# custom_line_V1_mux5.net
KiCad netlist of a schematic drawn in Altium Designer
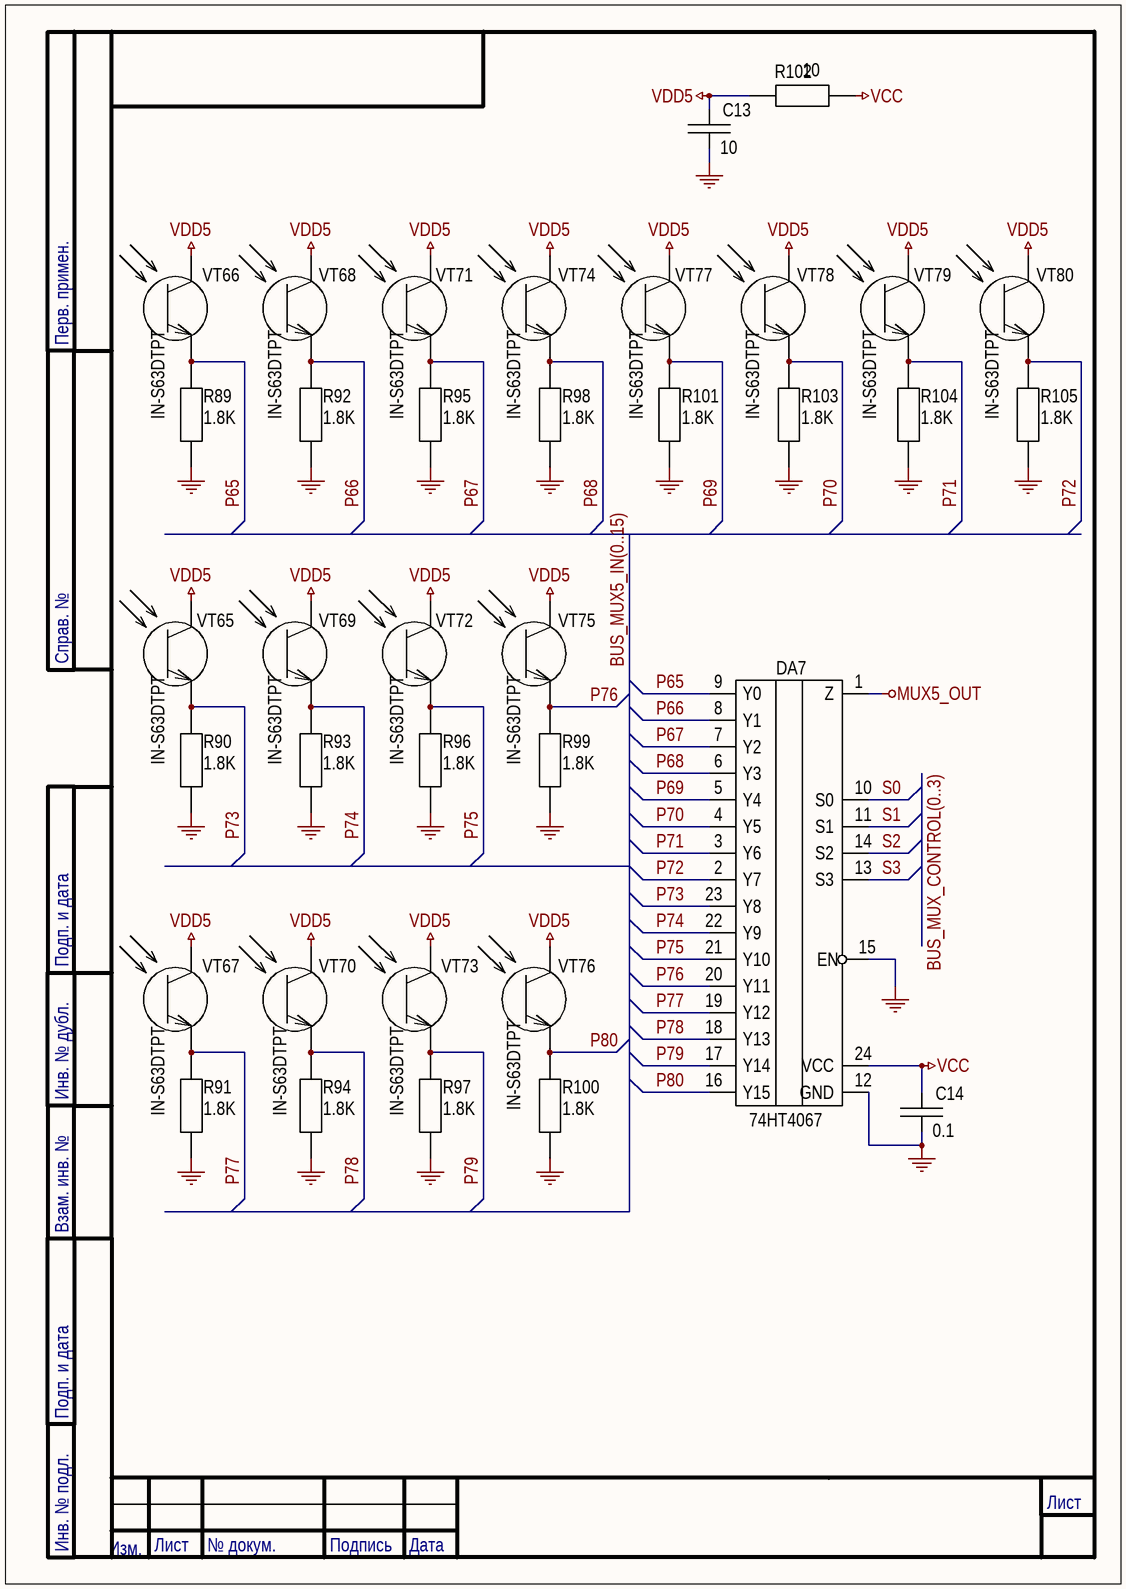
[diagram p0: custom_line_V1_mux5.SchDoc]

(export (version "E")
  (design (tool "Eeschema 10.0.6"))
  (components
    (comp (ref "C13") (value "10") (footprint "CC_0805") (libsource (lib "my_discrete_new") (part "C")))
    (comp (ref "C14") (value "0.1") (footprint "CC_0603") (libsource (lib "my_discrete_new") (part "C")))
    (comp (ref "DA7")
      (value "74HC4067")
      (footprint "TSSOP-24")
      (description "74HC4067PW")
      (fields (field (name "TYPE") "74HT4067"))
      (libsource (lib "my_microschems_new") (part "74HCT4067"))
    )
    (comp (ref "R89")
      (value "1.8K")
      (footprint "RC_0603_SMALL")
      (fields (field (name "POWER") "0.125W"))
      (libsource (lib "my_discrete_new") (part "R"))
    )
    (comp (ref "R90")
      (value "1.8K")
      (footprint "RC_0603_SMALL")
      (fields (field (name "POWER") "0.125W"))
      (libsource (lib "my_discrete_new") (part "R"))
    )
    (comp (ref "R91")
      (value "1.8K")
      (footprint "RC_0603_SMALL")
      (fields (field (name "POWER") "0.125W"))
      (libsource (lib "my_discrete_new") (part "R"))
    )
    (comp (ref "R92")
      (value "1.8K")
      (footprint "RC_0603_SMALL")
      (fields (field (name "POWER") "0.125W"))
      (libsource (lib "my_discrete_new") (part "R"))
    )
    (comp (ref "R93")
      (value "1.8K")
      (footprint "RC_0603_SMALL")
      (fields (field (name "POWER") "0.125W"))
      (libsource (lib "my_discrete_new") (part "R"))
    )
    (comp (ref "R94")
      (value "1.8K")
      (footprint "RC_0603_SMALL")
      (fields (field (name "POWER") "0.125W"))
      (libsource (lib "my_discrete_new") (part "R"))
    )
    (comp (ref "R95")
      (value "1.8K")
      (footprint "RC_0603_SMALL")
      (fields (field (name "POWER") "0.125W"))
      (libsource (lib "my_discrete_new") (part "R"))
    )
    (comp (ref "R96")
      (value "1.8K")
      (footprint "RC_0603_SMALL")
      (fields (field (name "POWER") "0.125W"))
      (libsource (lib "my_discrete_new") (part "R"))
    )
    (comp (ref "R97")
      (value "1.8K")
      (footprint "RC_0603_SMALL")
      (fields (field (name "POWER") "0.125W"))
      (libsource (lib "my_discrete_new") (part "R"))
    )
    (comp (ref "R98")
      (value "1.8K")
      (footprint "RC_0603_SMALL")
      (fields (field (name "POWER") "0.125W"))
      (libsource (lib "my_discrete_new") (part "R"))
    )
    (comp (ref "R99")
      (value "1.8K")
      (footprint "RC_0603_SMALL")
      (fields (field (name "POWER") "0.125W"))
      (libsource (lib "my_discrete_new") (part "R"))
    )
    (comp (ref "R100")
      (value "1.8K")
      (footprint "RC_0603_SMALL")
      (fields (field (name "POWER") "0.125W"))
      (libsource (lib "my_discrete_new") (part "R"))
    )
    (comp (ref "R101")
      (value "1.8K")
      (footprint "RC_0603_SMALL")
      (fields (field (name "POWER") "0.125W"))
      (libsource (lib "my_discrete_new") (part "R"))
    )
    (comp (ref "R102")
      (value "10")
      (footprint "RC_0603_SMALL")
      (fields (field (name "POWER") "0.125W"))
      (libsource (lib "my_discrete_new") (part "R"))
    )
    (comp (ref "R103")
      (value "1.8K")
      (footprint "RC_0603_SMALL")
      (fields (field (name "POWER") "0.125W"))
      (libsource (lib "my_discrete_new") (part "R"))
    )
    (comp (ref "R104")
      (value "1.8K")
      (footprint "RC_0603_SMALL")
      (fields (field (name "POWER") "0.125W"))
      (libsource (lib "my_discrete_new") (part "R"))
    )
    (comp (ref "R105")
      (value "1.8K")
      (footprint "RC_0603_SMALL")
      (fields (field (name "POWER") "0.125W"))
      (libsource (lib "my_discrete_new") (part "R"))
    )
    (comp (ref "VT65")
      (value "IN-S63DTPT")
      (footprint "LED_0603")
      (description "Phototransistor (Inolux)")
      (libsource (lib "my_discrete_new") (part "phototransistor"))
    )
    (comp (ref "VT66")
      (value "IN-S63DTPT")
      (footprint "LED_0603")
      (description "Phototransistor (Inolux)")
      (libsource (lib "my_discrete_new") (part "phototransistor"))
    )
    (comp (ref "VT67")
      (value "IN-S63DTPT")
      (footprint "LED_0603")
      (description "Phototransistor (Inolux)")
      (libsource (lib "my_discrete_new") (part "phototransistor"))
    )
    (comp (ref "VT68")
      (value "IN-S63DTPT")
      (footprint "LED_0603")
      (description "Phototransistor (Inolux)")
      (libsource (lib "my_discrete_new") (part "phototransistor"))
    )
    (comp (ref "VT69")
      (value "IN-S63DTPT")
      (footprint "LED_0603")
      (description "Phototransistor (Inolux)")
      (libsource (lib "my_discrete_new") (part "phototransistor"))
    )
    (comp (ref "VT70")
      (value "IN-S63DTPT")
      (footprint "LED_0603")
      (description "Phototransistor (Inolux)")
      (libsource (lib "my_discrete_new") (part "phototransistor"))
    )
    (comp (ref "VT71")
      (value "IN-S63DTPT")
      (footprint "LED_0603")
      (description "Phototransistor (Inolux)")
      (libsource (lib "my_discrete_new") (part "phototransistor"))
    )
    (comp (ref "VT72")
      (value "IN-S63DTPT")
      (footprint "LED_0603")
      (description "Phototransistor (Inolux)")
      (libsource (lib "my_discrete_new") (part "phototransistor"))
    )
    (comp (ref "VT73")
      (value "IN-S63DTPT")
      (footprint "LED_0603")
      (description "Phototransistor (Inolux)")
      (libsource (lib "my_discrete_new") (part "phototransistor"))
    )
    (comp (ref "VT74")
      (value "IN-S63DTPT")
      (footprint "LED_0603")
      (description "Phototransistor (Inolux)")
      (libsource (lib "my_discrete_new") (part "phototransistor"))
    )
    (comp (ref "VT75")
      (value "IN-S63DTPT")
      (footprint "LED_0603")
      (description "Phototransistor (Inolux)")
      (libsource (lib "my_discrete_new") (part "phototransistor"))
    )
    (comp (ref "VT76")
      (value "IN-S63DTPT")
      (footprint "LED_0603")
      (description "Phototransistor (Inolux)")
      (libsource (lib "my_discrete_new") (part "phototransistor"))
    )
    (comp (ref "VT77")
      (value "IN-S63DTPT")
      (footprint "LED_0603")
      (description "Phototransistor (Inolux)")
      (libsource (lib "my_discrete_new") (part "phototransistor"))
    )
    (comp (ref "VT78")
      (value "IN-S63DTPT")
      (footprint "LED_0603")
      (description "Phototransistor (Inolux)")
      (libsource (lib "my_discrete_new") (part "phototransistor"))
    )
    (comp (ref "VT79")
      (value "IN-S63DTPT")
      (footprint "LED_0603")
      (description "Phototransistor (Inolux)")
      (libsource (lib "my_discrete_new") (part "phototransistor"))
    )
    (comp (ref "VT80")
      (value "IN-S63DTPT")
      (footprint "LED_0603")
      (description "Phototransistor (Inolux)")
      (libsource (lib "my_discrete_new") (part "phototransistor"))
    )
  )
  (nets
    (net (code "3") (name "/P65") (class "Default")
      (node (ref "DA7") (pin "9") (pinfunction "Y0_9") (pintype "passive"))
      (node (ref "R89") (pin "2") (pinfunction "2_2") (pintype "passive"))
      (node (ref "VT66") (pin "2") (pinfunction "E_2") (pintype "passive"))
    )
    (net (code "4") (name "/P66") (class "Default")
      (node (ref "DA7") (pin "8") (pinfunction "Y1_8") (pintype "passive"))
      (node (ref "R92") (pin "2") (pinfunction "2_2") (pintype "passive"))
      (node (ref "VT68") (pin "2") (pinfunction "E_2") (pintype "passive"))
    )
    (net (code "5") (name "/P67") (class "Default")
      (node (ref "DA7") (pin "7") (pinfunction "Y2_7") (pintype "passive"))
      (node (ref "R95") (pin "2") (pinfunction "2_2") (pintype "passive"))
      (node (ref "VT71") (pin "2") (pinfunction "E_2") (pintype "passive"))
    )
    (net (code "6") (name "/P68") (class "Default")
      (node (ref "DA7") (pin "6") (pinfunction "Y3_6") (pintype "passive"))
      (node (ref "R98") (pin "2") (pinfunction "2_2") (pintype "passive"))
      (node (ref "VT74") (pin "2") (pinfunction "E_2") (pintype "passive"))
    )
    (net (code "7") (name "/P69") (class "Default")
      (node (ref "DA7") (pin "5") (pinfunction "Y4_5") (pintype "passive"))
      (node (ref "R101") (pin "2") (pinfunction "2_2") (pintype "passive"))
      (node (ref "VT77") (pin "2") (pinfunction "E_2") (pintype "passive"))
    )
    (net (code "8") (name "/P70") (class "Default")
      (node (ref "DA7") (pin "4") (pinfunction "Y5_4") (pintype "passive"))
      (node (ref "R103") (pin "2") (pinfunction "2_2") (pintype "passive"))
      (node (ref "VT78") (pin "2") (pinfunction "E_2") (pintype "passive"))
    )
    (net (code "9") (name "/P71") (class "Default")
      (node (ref "DA7") (pin "3") (pinfunction "Y6_3") (pintype "passive"))
      (node (ref "R104") (pin "2") (pinfunction "2_2") (pintype "passive"))
      (node (ref "VT79") (pin "2") (pinfunction "E_2") (pintype "passive"))
    )
    (net (code "10") (name "/P72") (class "Default")
      (node (ref "DA7") (pin "2") (pinfunction "Y7_2") (pintype "passive"))
      (node (ref "R105") (pin "2") (pinfunction "2_2") (pintype "passive"))
      (node (ref "VT80") (pin "2") (pinfunction "E_2") (pintype "passive"))
    )
    (net (code "11") (name "/P73") (class "Default")
      (node (ref "DA7") (pin "23") (pinfunction "Y8_23") (pintype "passive"))
      (node (ref "R90") (pin "2") (pinfunction "2_2") (pintype "passive"))
      (node (ref "VT65") (pin "2") (pinfunction "E_2") (pintype "passive"))
    )
    (net (code "12") (name "/P74") (class "Default")
      (node (ref "DA7") (pin "22") (pinfunction "Y9_22") (pintype "passive"))
      (node (ref "R93") (pin "2") (pinfunction "2_2") (pintype "passive"))
      (node (ref "VT69") (pin "2") (pinfunction "E_2") (pintype "passive"))
    )
    (net (code "13") (name "/P75") (class "Default")
      (node (ref "DA7") (pin "21") (pinfunction "Y10_21") (pintype "passive"))
      (node (ref "R96") (pin "2") (pinfunction "2_2") (pintype "passive"))
      (node (ref "VT72") (pin "2") (pinfunction "E_2") (pintype "passive"))
    )
    (net (code "14") (name "/P76") (class "Default")
      (node (ref "DA7") (pin "20") (pinfunction "Y11_20") (pintype "passive"))
      (node (ref "R99") (pin "2") (pinfunction "2_2") (pintype "passive"))
      (node (ref "VT75") (pin "2") (pinfunction "E_2") (pintype "passive"))
    )
    (net (code "15") (name "/P77") (class "Default")
      (node (ref "DA7") (pin "19") (pinfunction "Y12_19") (pintype "passive"))
      (node (ref "R91") (pin "2") (pinfunction "2_2") (pintype "passive"))
      (node (ref "VT67") (pin "2") (pinfunction "E_2") (pintype "passive"))
    )
    (net (code "16") (name "/P78") (class "Default")
      (node (ref "DA7") (pin "18") (pinfunction "Y13_18") (pintype "passive"))
      (node (ref "R94") (pin "2") (pinfunction "2_2") (pintype "passive"))
      (node (ref "VT70") (pin "2") (pinfunction "E_2") (pintype "passive"))
    )
    (net (code "17") (name "/P79") (class "Default")
      (node (ref "DA7") (pin "17") (pinfunction "Y14_17") (pintype "passive"))
      (node (ref "R97") (pin "2") (pinfunction "2_2") (pintype "passive"))
      (node (ref "VT73") (pin "2") (pinfunction "E_2") (pintype "passive"))
    )
    (net (code "18") (name "/P80") (class "Default")
      (node (ref "DA7") (pin "16") (pinfunction "Y15_16") (pintype "passive"))
      (node (ref "R100") (pin "2") (pinfunction "2_2") (pintype "passive"))
      (node (ref "VT76") (pin "2") (pinfunction "E_2") (pintype "passive"))
    )
    (net (code "19") (name "/S0") (class "Default")
      (node (ref "DA7") (pin "10") (pinfunction "S0_10") (pintype "passive"))
    )
    (net (code "20") (name "/S1") (class "Default")
      (node (ref "DA7") (pin "11") (pinfunction "S1_11") (pintype "passive"))
    )
    (net (code "21") (name "/S2") (class "Default")
      (node (ref "DA7") (pin "14") (pinfunction "S2_14") (pintype "passive"))
    )
    (net (code "22") (name "/S3") (class "Default")
      (node (ref "DA7") (pin "13") (pinfunction "S3_13") (pintype "passive"))
    )
    (net (code "25") (name "GND") (class "Default")
      (node (ref "C13") (pin "1") (pinfunction "1_1") (pintype "passive"))
      (node (ref "C14") (pin "1") (pinfunction "1_1") (pintype "passive"))
      (node (ref "DA7") (pin "12") (pinfunction "GND_12") (pintype "power_in"))
      (node (ref "DA7") (pin "15") (pinfunction "EN_15") (pintype "passive"))
      (node (ref "R100") (pin "1") (pinfunction "1_1") (pintype "passive"))
      (node (ref "R101") (pin "1") (pinfunction "1_1") (pintype "passive"))
      (node (ref "R103") (pin "1") (pinfunction "1_1") (pintype "passive"))
      (node (ref "R104") (pin "1") (pinfunction "1_1") (pintype "passive"))
      (node (ref "R105") (pin "1") (pinfunction "1_1") (pintype "passive"))
      (node (ref "R89") (pin "1") (pinfunction "1_1") (pintype "passive"))
      (node (ref "R90") (pin "1") (pinfunction "1_1") (pintype "passive"))
      (node (ref "R91") (pin "1") (pinfunction "1_1") (pintype "passive"))
      (node (ref "R92") (pin "1") (pinfunction "1_1") (pintype "passive"))
      (node (ref "R93") (pin "1") (pinfunction "1_1") (pintype "passive"))
      (node (ref "R94") (pin "1") (pinfunction "1_1") (pintype "passive"))
      (node (ref "R95") (pin "1") (pinfunction "1_1") (pintype "passive"))
      (node (ref "R96") (pin "1") (pinfunction "1_1") (pintype "passive"))
      (node (ref "R97") (pin "1") (pinfunction "1_1") (pintype "passive"))
      (node (ref "R98") (pin "1") (pinfunction "1_1") (pintype "passive"))
      (node (ref "R99") (pin "1") (pinfunction "1_1") (pintype "passive"))
    )
    (net (code "26") (name "MUX5_OUT") (class "Default")
      (node (ref "DA7") (pin "1") (pinfunction "Z_1") (pintype "passive"))
    )
    (net (code "27") (name "VCC") (class "Default")
      (node (ref "C14") (pin "2") (pinfunction "2_2") (pintype "passive"))
      (node (ref "DA7") (pin "24") (pinfunction "VCC_24") (pintype "power_in"))
      (node (ref "R102") (pin "1") (pinfunction "1_1") (pintype "passive"))
    )
    (net (code "28") (name "VDD5") (class "Default")
      (node (ref "C13") (pin "2") (pinfunction "2_2") (pintype "passive"))
      (node (ref "R102") (pin "2") (pinfunction "2_2") (pintype "passive"))
      (node (ref "VT65") (pin "1") (pinfunction "C_1") (pintype "passive"))
      (node (ref "VT66") (pin "1") (pinfunction "C_1") (pintype "passive"))
      (node (ref "VT67") (pin "1") (pinfunction "C_1") (pintype "passive"))
      (node (ref "VT68") (pin "1") (pinfunction "C_1") (pintype "passive"))
      (node (ref "VT69") (pin "1") (pinfunction "C_1") (pintype "passive"))
      (node (ref "VT70") (pin "1") (pinfunction "C_1") (pintype "passive"))
      (node (ref "VT71") (pin "1") (pinfunction "C_1") (pintype "passive"))
      (node (ref "VT72") (pin "1") (pinfunction "C_1") (pintype "passive"))
      (node (ref "VT73") (pin "1") (pinfunction "C_1") (pintype "passive"))
      (node (ref "VT74") (pin "1") (pinfunction "C_1") (pintype "passive"))
      (node (ref "VT75") (pin "1") (pinfunction "C_1") (pintype "passive"))
      (node (ref "VT76") (pin "1") (pinfunction "C_1") (pintype "passive"))
      (node (ref "VT77") (pin "1") (pinfunction "C_1") (pintype "passive"))
      (node (ref "VT78") (pin "1") (pinfunction "C_1") (pintype "passive"))
      (node (ref "VT79") (pin "1") (pinfunction "C_1") (pintype "passive"))
      (node (ref "VT80") (pin "1") (pinfunction "C_1") (pintype "passive"))
    )
  )
)
